# Qwiic_Solid_State_Relay.net
KiCad netlist of a schematic drawn in EAGLE
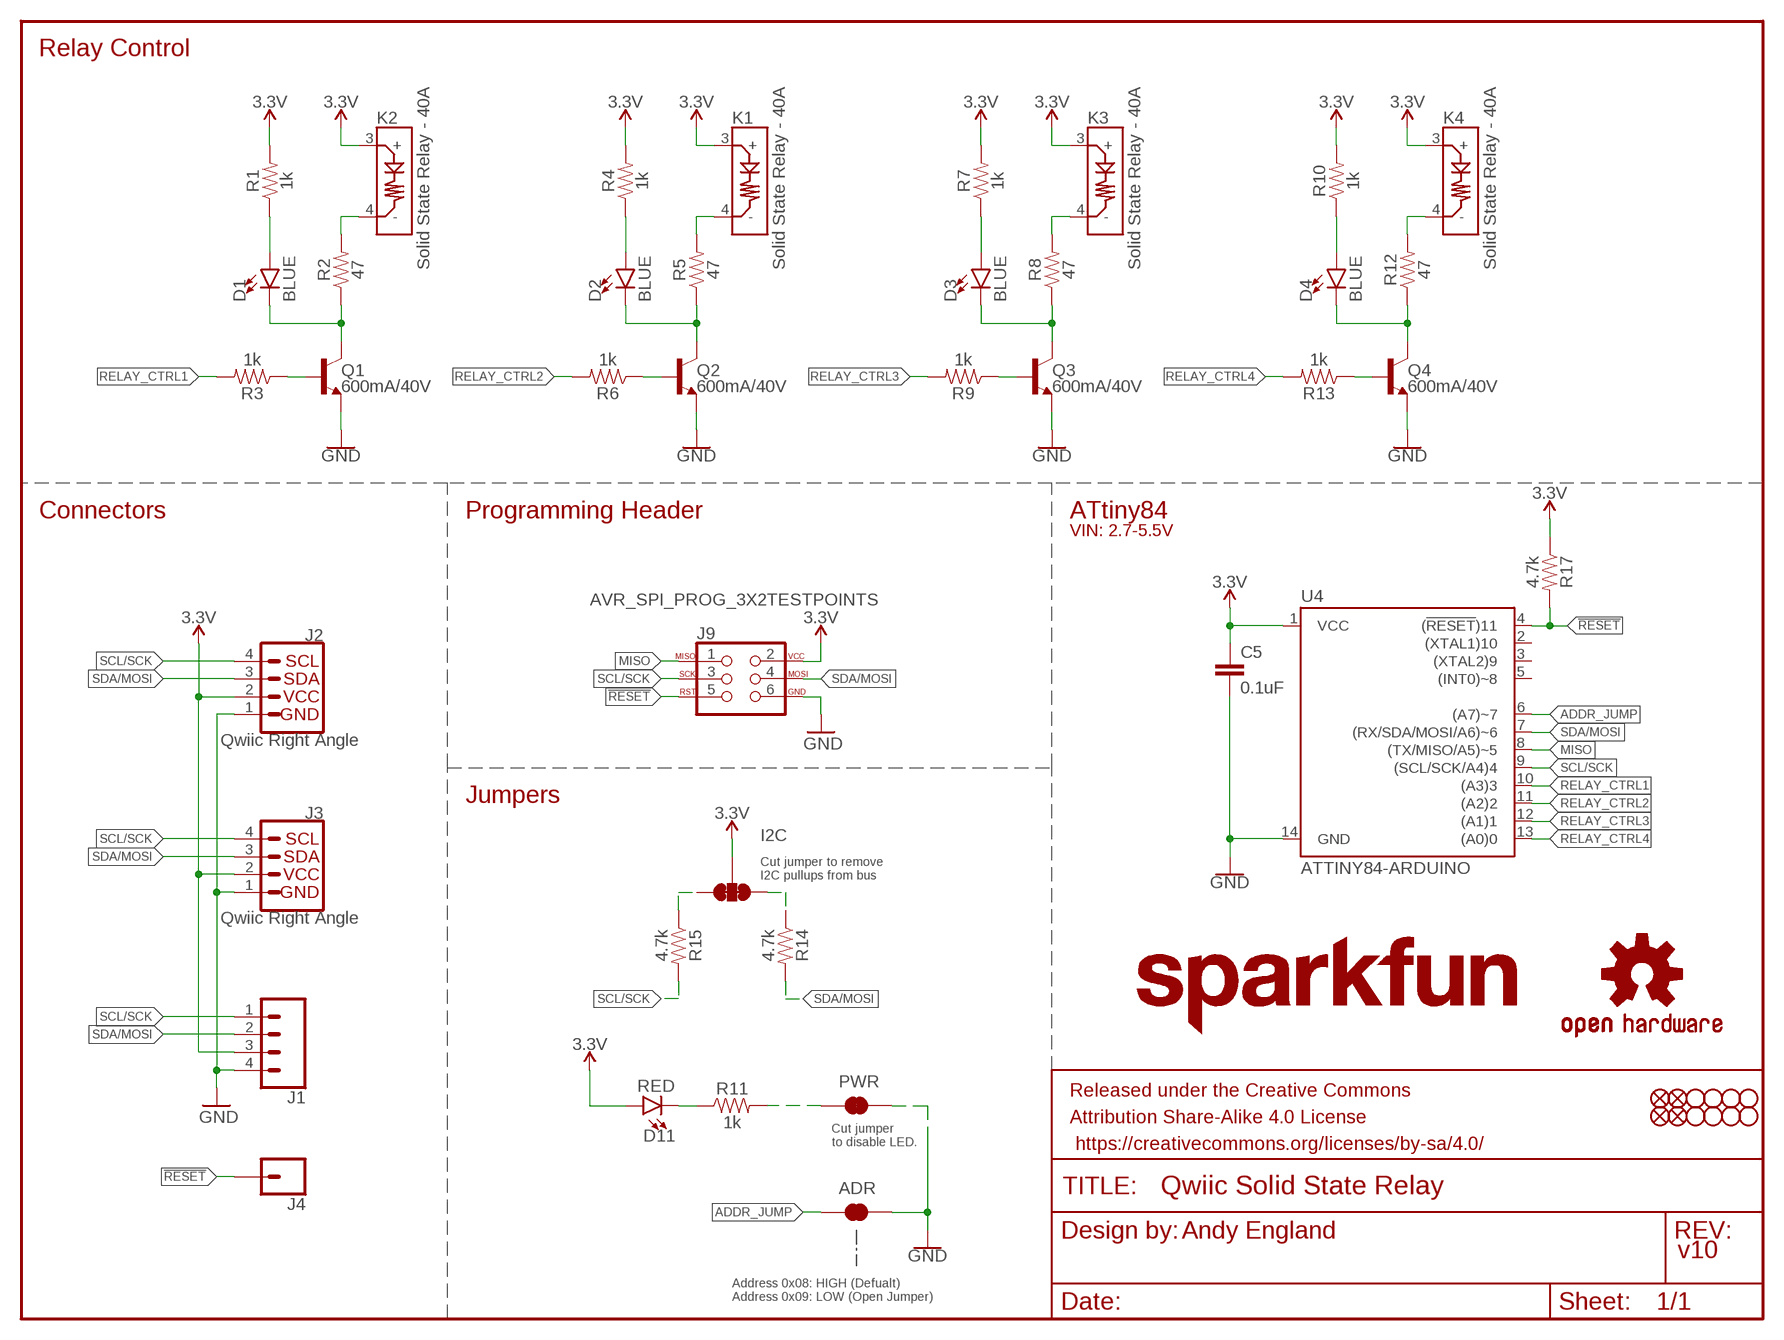
[diagram p0: schematic, sheet 1]

(export (version "E")
  (design (tool "Eeschema 10.0.6"))
  (components
    (comp (ref "ADR")
      (value "JUMPER-SMT_2_NC_TRACE_SILK")
      (footprint "eagle-import:SMT-JUMPER_2_NC_TRACE_SILK")
      (libsource (lib "eagle-import") (part "JUMPER-SMT_2_NC_TRACE_SILK"))
    )
    (comp (ref "C5")
      (value "0.1uF")
      (footprint "eagle-import:0603")
      (libsource (lib "eagle-import") (part "0.1UF-0603-25V-(+80/-20%)"))
    )
    (comp (ref "D1")
      (value "BLUE")
      (footprint "eagle-import:LED-0603")
      (libsource (lib "eagle-import") (part "LED-BLUE0603"))
    )
    (comp (ref "D2")
      (value "BLUE")
      (footprint "eagle-import:LED-0603")
      (libsource (lib "eagle-import") (part "LED-BLUE0603"))
    )
    (comp (ref "D3")
      (value "BLUE")
      (footprint "eagle-import:LED-0603")
      (libsource (lib "eagle-import") (part "LED-BLUE0603"))
    )
    (comp (ref "D4")
      (value "BLUE")
      (footprint "eagle-import:LED-0603")
      (libsource (lib "eagle-import") (part "LED-BLUE0603"))
    )
    (comp (ref "D11")
      (value "RED")
      (footprint "eagle-import:LED-0603")
      (libsource (lib "eagle-import") (part "LED-RED0603"))
    )
    (comp (ref "FD1")
      (value "FIDUCIAL1X2")
      (footprint "eagle-import:FIDUCIAL-1X2")
      (libsource (lib "eagle-import") (part "FIDUCIAL1X2"))
    )
    (comp (ref "FD2")
      (value "FIDUCIAL1X2")
      (footprint "eagle-import:FIDUCIAL-1X2")
      (libsource (lib "eagle-import") (part "FIDUCIAL1X2"))
    )
    (comp (ref "FD3")
      (value "FIDUCIAL1X2")
      (footprint "eagle-import:FIDUCIAL-1X2")
      (libsource (lib "eagle-import") (part "FIDUCIAL1X2"))
    )
    (comp (ref "FD4")
      (value "FIDUCIAL1X2")
      (footprint "eagle-import:FIDUCIAL-1X2")
      (libsource (lib "eagle-import") (part "FIDUCIAL1X2"))
    )
    (comp (ref "FRAME1")
      (value "FRAME-LETTER")
      (footprint "eagle-import:CREATIVE_COMMONS")
      (libsource (lib "eagle-import") (part "FRAME-LETTER"))
    )
    (comp (ref "I2C")
      (value "JUMPER-SMT_3_2-NC_TRACE_SILK")
      (footprint "eagle-import:SMT-JUMPER_3_2-NC_TRACE_SILK")
      (libsource (lib "eagle-import") (part "JUMPER-SMT_3_2-NC_TRACE_SILK"))
    )
    (comp (ref "J1")
      (value "CONN_041X04_NO_SILK")
      (footprint "eagle-import:1X04_NO_SILK")
      (libsource (lib "eagle-import") (part "CONN_041X04_NO_SILK"))
    )
    (comp (ref "J2")
      (value "Qwiic Right Angle")
      (footprint "eagle-import:JST04_1MM_RA")
      (libsource (lib "eagle-import") (part "I2C_STANDARDQWIIC"))
    )
    (comp (ref "J3")
      (value "Qwiic Right Angle")
      (footprint "eagle-import:JST04_1MM_RA")
      (libsource (lib "eagle-import") (part "I2C_STANDARDQWIIC"))
    )
    (comp (ref "J4")
      (value "CONN_01PTH_NO_SILK_YES_STOP")
      (footprint "eagle-import:1X01_NO_SILK")
      (libsource (lib "eagle-import") (part "CONN_01PTH_NO_SILK_YES_STOP"))
    )
    (comp (ref "J9")
      (value "AVR_SPI_PROG_3X2TESTPOINTS")
      (footprint "eagle-import:2X3_TEST_POINTS")
      (libsource (lib "eagle-import") (part "AVR_SPI_PROG_3X2TESTPOINTS"))
    )
    (comp (ref "JP1")
      (value "STAND-OFF")
      (footprint "eagle-import:STAND-OFF")
      (libsource (lib "eagle-import") (part "STAND-OFF"))
    )
    (comp (ref "JP2")
      (value "STAND-OFF")
      (footprint "eagle-import:STAND-OFF")
      (libsource (lib "eagle-import") (part "STAND-OFF"))
    )
    (comp (ref "JP3")
      (value "STAND-OFF")
      (footprint "eagle-import:STAND-OFF")
      (libsource (lib "eagle-import") (part "STAND-OFF"))
    )
    (comp (ref "JP4")
      (value "STAND-OFF")
      (footprint "eagle-import:STAND-OFF")
      (libsource (lib "eagle-import") (part "STAND-OFF"))
    )
    (comp (ref "JP5")
      (value "STAND-OFF")
      (footprint "eagle-import:STAND-OFF")
      (libsource (lib "eagle-import") (part "STAND-OFF"))
    )
    (comp (ref "JP6")
      (value "STAND-OFF")
      (footprint "eagle-import:STAND-OFF")
      (libsource (lib "eagle-import") (part "STAND-OFF"))
    )
    (comp (ref "JP7")
      (value "STAND-OFF")
      (footprint "eagle-import:STAND-OFF")
      (libsource (lib "eagle-import") (part "STAND-OFF"))
    )
    (comp (ref "JP8")
      (value "STAND-OFF")
      (footprint "eagle-import:STAND-OFF")
      (libsource (lib "eagle-import") (part "STAND-OFF"))
    )
    (comp (ref "K1")
      (value "Solid State Relay - 40A")
      (footprint "eagle-import:SSR-40DA-H")
      (libsource (lib "eagle-import") (part "SOLID_STATE_RELAY_SSR-40DA-H"))
    )
    (comp (ref "K2")
      (value "Solid State Relay - 40A")
      (footprint "eagle-import:SSR-40DA-H")
      (libsource (lib "eagle-import") (part "SOLID_STATE_RELAY_SSR-40DA-H"))
    )
    (comp (ref "K3")
      (value "Solid State Relay - 40A")
      (footprint "eagle-import:SSR-40DA-H")
      (libsource (lib "eagle-import") (part "SOLID_STATE_RELAY_SSR-40DA-H"))
    )
    (comp (ref "K4")
      (value "Solid State Relay - 40A")
      (footprint "eagle-import:SSR-40DA-H")
      (libsource (lib "eagle-import") (part "SOLID_STATE_RELAY_SSR-40DA-H"))
    )
    (comp (ref "LOGO1")
      (value "SFE_LOGO_NAME1_INCH")
      (footprint "eagle-import:SFE_LOGO_NAME_1")
      (libsource (lib "eagle-import") (part "SFE_LOGO_NAME1_INCH"))
    )
    (comp (ref "LOGO2")
      (value "OSHW-LOGOS")
      (footprint "eagle-import:OSHW-LOGO-S")
      (libsource (lib "eagle-import") (part "OSHW-LOGOS"))
    )
    (comp (ref "PWR")
      (value "JUMPER-SMT_2_NC_TRACE_SILK")
      (footprint "eagle-import:SMT-JUMPER_2_NC_TRACE_SILK")
      (libsource (lib "eagle-import") (part "JUMPER-SMT_2_NC_TRACE_SILK"))
    )
    (comp (ref "Q1")
      (value "600mA/40V")
      (footprint "eagle-import:SOT23-3")
      (libsource (lib "eagle-import") (part "TRANS_NPN-MMBT2222AL"))
    )
    (comp (ref "Q2")
      (value "600mA/40V")
      (footprint "eagle-import:SOT23-3")
      (libsource (lib "eagle-import") (part "TRANS_NPN-MMBT2222AL"))
    )
    (comp (ref "Q3")
      (value "600mA/40V")
      (footprint "eagle-import:SOT23-3")
      (libsource (lib "eagle-import") (part "TRANS_NPN-MMBT2222AL"))
    )
    (comp (ref "Q4")
      (value "600mA/40V")
      (footprint "eagle-import:SOT23-3")
      (libsource (lib "eagle-import") (part "TRANS_NPN-MMBT2222AL"))
    )
    (comp (ref "R1")
      (value "1k")
      (footprint "eagle-import:0603")
      (libsource (lib "eagle-import") (part "1KOHM-0603-1/10W-1%"))
    )
    (comp (ref "R2")
      (value "47")
      (footprint "eagle-import:0603")
      (libsource (lib "eagle-import") (part "47OHM-0603-1/10W-1%"))
    )
    (comp (ref "R3")
      (value "1k")
      (footprint "eagle-import:0603")
      (libsource (lib "eagle-import") (part "1KOHM-0603-1/10W-1%"))
    )
    (comp (ref "R4")
      (value "1k")
      (footprint "eagle-import:0603")
      (libsource (lib "eagle-import") (part "1KOHM-0603-1/10W-1%"))
    )
    (comp (ref "R5")
      (value "47")
      (footprint "eagle-import:0603")
      (libsource (lib "eagle-import") (part "47OHM-0603-1/10W-1%"))
    )
    (comp (ref "R6")
      (value "1k")
      (footprint "eagle-import:0603")
      (libsource (lib "eagle-import") (part "1KOHM-0603-1/10W-1%"))
    )
    (comp (ref "R7")
      (value "1k")
      (footprint "eagle-import:0603")
      (libsource (lib "eagle-import") (part "1KOHM-0603-1/10W-1%"))
    )
    (comp (ref "R8")
      (value "47")
      (footprint "eagle-import:0603")
      (libsource (lib "eagle-import") (part "47OHM-0603-1/10W-1%"))
    )
    (comp (ref "R9")
      (value "1k")
      (footprint "eagle-import:0603")
      (libsource (lib "eagle-import") (part "1KOHM-0603-1/10W-1%"))
    )
    (comp (ref "R10")
      (value "1k")
      (footprint "eagle-import:0603")
      (libsource (lib "eagle-import") (part "1KOHM-0603-1/10W-1%"))
    )
    (comp (ref "R11")
      (value "1k")
      (footprint "eagle-import:0603")
      (libsource (lib "eagle-import") (part "1KOHM-0603-1/10W-1%"))
    )
    (comp (ref "R12")
      (value "47")
      (footprint "eagle-import:0603")
      (libsource (lib "eagle-import") (part "47OHM-0603-1/10W-1%"))
    )
    (comp (ref "R13")
      (value "1k")
      (footprint "eagle-import:0603")
      (libsource (lib "eagle-import") (part "1KOHM-0603-1/10W-1%"))
    )
    (comp (ref "R14")
      (value "4.7k")
      (footprint "eagle-import:0603")
      (libsource (lib "eagle-import") (part "4.7KOHM-0603-1/10W-1%"))
    )
    (comp (ref "R15")
      (value "4.7k")
      (footprint "eagle-import:0603")
      (libsource (lib "eagle-import") (part "4.7KOHM-0603-1/10W-1%"))
    )
    (comp (ref "R17")
      (value "4.7k")
      (footprint "eagle-import:0603")
      (libsource (lib "eagle-import") (part "4.7KOHM-0603-1/10W-1%"))
    )
    (comp (ref "U4")
      (value "ATTINY84-ARDUINO")
      (footprint "eagle-import:SO14")
      (libsource (lib "eagle-import") (part "ATTINY84-ARDUINO"))
    )
  )
  (nets
    (net (code "1") (name "/~{RESET}") (class "Default")
      (node (ref "J4") (pin "1") (pinfunction "1_1") (pintype "passive"))
      (node (ref "J9") (pin "5") (pinfunction "5_5") (pintype "passive"))
      (node (ref "R17") (pin "2") (pinfunction "2_2") (pintype "passive"))
      (node (ref "U4") (pin "4") (pinfunction "(~{RESET})11_4") (pintype "bidirectional"))
    )
    (net (code "2") (name "3.3V") (class "Default")
      (node (ref "C5") (pin "1") (pinfunction "1_1") (pintype "passive"))
      (node (ref "D11") (pin "A") (pinfunction "A_A") (pintype "passive"))
      (node (ref "I2C") (pin "2") (pinfunction "2_2") (pintype "passive"))
      (node (ref "J1") (pin "3") (pinfunction "3_3") (pintype "passive"))
      (node (ref "J2") (pin "2") (pinfunction "2_2") (pintype "power_in"))
      (node (ref "J3") (pin "2") (pinfunction "2_2") (pintype "power_in"))
      (node (ref "J9") (pin "2") (pinfunction "2_2") (pintype "passive"))
      (node (ref "K1") (pin "3") (pinfunction "+_3") (pintype "bidirectional"))
      (node (ref "K2") (pin "3") (pinfunction "+_3") (pintype "bidirectional"))
      (node (ref "K3") (pin "3") (pinfunction "+_3") (pintype "bidirectional"))
      (node (ref "K4") (pin "3") (pinfunction "+_3") (pintype "bidirectional"))
      (node (ref "R1") (pin "2") (pinfunction "2_2") (pintype "passive"))
      (node (ref "R10") (pin "2") (pinfunction "2_2") (pintype "passive"))
      (node (ref "R17") (pin "1") (pinfunction "1_1") (pintype "passive"))
      (node (ref "R4") (pin "2") (pinfunction "2_2") (pintype "passive"))
      (node (ref "R7") (pin "2") (pinfunction "2_2") (pintype "passive"))
      (node (ref "U4") (pin "1") (pinfunction "VCC_1") (pintype "bidirectional"))
    )
    (net (code "3") (name "ADDR_JUMP") (class "Default")
      (node (ref "ADR") (pin "1") (pinfunction "1_1") (pintype "passive"))
      (node (ref "U4") (pin "6") (pinfunction "(A7)~{7}_6") (pintype "bidirectional"))
    )
    (net (code "4") (name "GND") (class "Default")
      (node (ref "ADR") (pin "2") (pinfunction "2_2") (pintype "passive"))
      (node (ref "C5") (pin "2") (pinfunction "2_2") (pintype "passive"))
      (node (ref "J1") (pin "4") (pinfunction "4_4") (pintype "passive"))
      (node (ref "J2") (pin "1") (pinfunction "1_1") (pintype "power_in"))
      (node (ref "J3") (pin "1") (pinfunction "1_1") (pintype "power_in"))
      (node (ref "J9") (pin "6") (pinfunction "6_6") (pintype "passive"))
      (node (ref "PWR") (pin "1") (pinfunction "1_1") (pintype "passive"))
      (node (ref "Q1") (pin "2") (pinfunction "E_2") (pintype "passive"))
      (node (ref "Q2") (pin "2") (pinfunction "E_2") (pintype "passive"))
      (node (ref "Q3") (pin "2") (pinfunction "E_2") (pintype "passive"))
      (node (ref "Q4") (pin "2") (pinfunction "E_2") (pintype "passive"))
      (node (ref "U4") (pin "14") (pinfunction "GND_14") (pintype "bidirectional"))
    )
    (net (code "5") (name "MISO") (class "Default")
      (node (ref "J9") (pin "1") (pinfunction "1_1") (pintype "passive"))
      (node (ref "U4") (pin "8") (pinfunction "(TX/MISO/A5)~{5}_8") (pintype "bidirectional"))
    )
    (net (code "6") (name "Net-(D1-PadA)") (class "Default")
      (node (ref "D1") (pin "A") (pinfunction "A_A") (pintype "passive"))
      (node (ref "R1") (pin "1") (pinfunction "1_1") (pintype "passive"))
    )
    (net (code "7") (name "Net-(D2-PadA)") (class "Default")
      (node (ref "D2") (pin "A") (pinfunction "A_A") (pintype "passive"))
      (node (ref "R4") (pin "1") (pinfunction "1_1") (pintype "passive"))
    )
    (net (code "8") (name "Net-(D3-PadA)") (class "Default")
      (node (ref "D3") (pin "A") (pinfunction "A_A") (pintype "passive"))
      (node (ref "R7") (pin "1") (pinfunction "1_1") (pintype "passive"))
    )
    (net (code "9") (name "Net-(D4-PadA)") (class "Default")
      (node (ref "D4") (pin "A") (pinfunction "A_A") (pintype "passive"))
      (node (ref "R10") (pin "1") (pinfunction "1_1") (pintype "passive"))
    )
    (net (code "10") (name "Net-(D11-PadC)") (class "Default")
      (node (ref "D11") (pin "C") (pinfunction "C_C") (pintype "passive"))
      (node (ref "R11") (pin "1") (pinfunction "1_1") (pintype "passive"))
    )
    (net (code "11") (name "Net-(I2C-Pad1)") (class "Default")
      (node (ref "I2C") (pin "1") (pinfunction "1_1") (pintype "passive"))
      (node (ref "R14") (pin "1") (pinfunction "1_1") (pintype "passive"))
    )
    (net (code "12") (name "Net-(I2C-Pad3)") (class "Default")
      (node (ref "I2C") (pin "3") (pinfunction "3_3") (pintype "passive"))
      (node (ref "R15") (pin "1") (pinfunction "1_1") (pintype "passive"))
    )
    (net (code "13") (name "Net-(K1--)") (class "Default")
      (node (ref "K1") (pin "4") (pinfunction "-_4") (pintype "bidirectional"))
      (node (ref "R5") (pin "2") (pinfunction "2_2") (pintype "passive"))
    )
    (net (code "14") (name "Net-(K2--)") (class "Default")
      (node (ref "K2") (pin "4") (pinfunction "-_4") (pintype "bidirectional"))
      (node (ref "R2") (pin "2") (pinfunction "2_2") (pintype "passive"))
    )
    (net (code "15") (name "Net-(K3--)") (class "Default")
      (node (ref "K3") (pin "4") (pinfunction "-_4") (pintype "bidirectional"))
      (node (ref "R8") (pin "2") (pinfunction "2_2") (pintype "passive"))
    )
    (net (code "16") (name "Net-(K4--)") (class "Default")
      (node (ref "K4") (pin "4") (pinfunction "-_4") (pintype "bidirectional"))
      (node (ref "R12") (pin "2") (pinfunction "2_2") (pintype "passive"))
    )
    (net (code "17") (name "Net-(PWR-Pad2)") (class "Default")
      (node (ref "PWR") (pin "2") (pinfunction "2_2") (pintype "passive"))
      (node (ref "R11") (pin "2") (pinfunction "2_2") (pintype "passive"))
    )
    (net (code "18") (name "Net-(Q1-B)") (class "Default")
      (node (ref "Q1") (pin "1") (pinfunction "B_1") (pintype "passive"))
      (node (ref "R3") (pin "1") (pinfunction "1_1") (pintype "passive"))
    )
    (net (code "19") (name "Net-(Q1-C)") (class "Default")
      (node (ref "D1") (pin "C") (pinfunction "C_C") (pintype "passive"))
      (node (ref "Q1") (pin "3") (pinfunction "C_3") (pintype "passive"))
      (node (ref "R2") (pin "1") (pinfunction "1_1") (pintype "passive"))
    )
    (net (code "20") (name "Net-(Q2-B)") (class "Default")
      (node (ref "Q2") (pin "1") (pinfunction "B_1") (pintype "passive"))
      (node (ref "R6") (pin "1") (pinfunction "1_1") (pintype "passive"))
    )
    (net (code "21") (name "Net-(Q2-C)") (class "Default")
      (node (ref "D2") (pin "C") (pinfunction "C_C") (pintype "passive"))
      (node (ref "Q2") (pin "3") (pinfunction "C_3") (pintype "passive"))
      (node (ref "R5") (pin "1") (pinfunction "1_1") (pintype "passive"))
    )
    (net (code "22") (name "Net-(Q3-B)") (class "Default")
      (node (ref "Q3") (pin "1") (pinfunction "B_1") (pintype "passive"))
      (node (ref "R9") (pin "1") (pinfunction "1_1") (pintype "passive"))
    )
    (net (code "23") (name "Net-(Q3-C)") (class "Default")
      (node (ref "D3") (pin "C") (pinfunction "C_C") (pintype "passive"))
      (node (ref "Q3") (pin "3") (pinfunction "C_3") (pintype "passive"))
      (node (ref "R8") (pin "1") (pinfunction "1_1") (pintype "passive"))
    )
    (net (code "24") (name "Net-(Q4-B)") (class "Default")
      (node (ref "Q4") (pin "1") (pinfunction "B_1") (pintype "passive"))
      (node (ref "R13") (pin "1") (pinfunction "1_1") (pintype "passive"))
    )
    (net (code "25") (name "Net-(Q4-C)") (class "Default")
      (node (ref "D4") (pin "C") (pinfunction "C_C") (pintype "passive"))
      (node (ref "Q4") (pin "3") (pinfunction "C_3") (pintype "passive"))
      (node (ref "R12") (pin "1") (pinfunction "1_1") (pintype "passive"))
    )
    (net (code "26") (name "RELAY_CTRL1") (class "Default")
      (node (ref "R3") (pin "2") (pinfunction "2_2") (pintype "passive"))
      (node (ref "U4") (pin "10") (pinfunction "(A3)3_10") (pintype "bidirectional"))
    )
    (net (code "27") (name "RELAY_CTRL2") (class "Default")
      (node (ref "R6") (pin "2") (pinfunction "2_2") (pintype "passive"))
      (node (ref "U4") (pin "11") (pinfunction "(A2)2_11") (pintype "bidirectional"))
    )
    (net (code "28") (name "RELAY_CTRL3") (class "Default")
      (node (ref "R9") (pin "2") (pinfunction "2_2") (pintype "passive"))
      (node (ref "U4") (pin "12") (pinfunction "(A1)1_12") (pintype "bidirectional"))
    )
    (net (code "29") (name "RELAY_CTRL4") (class "Default")
      (node (ref "R13") (pin "2") (pinfunction "2_2") (pintype "passive"))
      (node (ref "U4") (pin "13") (pinfunction "(A0)0_13") (pintype "bidirectional"))
    )
    (net (code "30") (name "SCL{slash}SCK") (class "Default")
      (node (ref "J1") (pin "1") (pinfunction "1_1") (pintype "passive"))
      (node (ref "J2") (pin "4") (pinfunction "4_4") (pintype "passive"))
      (node (ref "J3") (pin "4") (pinfunction "4_4") (pintype "passive"))
      (node (ref "J9") (pin "3") (pinfunction "3_3") (pintype "passive"))
      (node (ref "R15") (pin "2") (pinfunction "2_2") (pintype "passive"))
      (node (ref "U4") (pin "9") (pinfunction "(SCL/SCK/A4)4_9") (pintype "bidirectional"))
    )
    (net (code "31") (name "SDA{slash}MOSI") (class "Default")
      (node (ref "J1") (pin "2") (pinfunction "2_2") (pintype "passive"))
      (node (ref "J2") (pin "3") (pinfunction "3_3") (pintype "passive"))
      (node (ref "J3") (pin "3") (pinfunction "3_3") (pintype "passive"))
      (node (ref "J9") (pin "4") (pinfunction "4_4") (pintype "passive"))
      (node (ref "R14") (pin "2") (pinfunction "2_2") (pintype "passive"))
      (node (ref "U4") (pin "7") (pinfunction "(RX/SDA/MOSI/A6)~{6}_7") (pintype "bidirectional"))
    )
    (net (code "32") (name "unconnected-(U4-(INT0)~{8}-Pad5)") (class "Default")
      (node (ref "U4") (pin "5") (pinfunction "(INT0)~{8}_5") (pintype "bidirectional"))
    )
    (net (code "33") (name "unconnected-(U4-(XTAL1)10-Pad2)") (class "Default")
      (node (ref "U4") (pin "2") (pinfunction "(XTAL1)10_2") (pintype "bidirectional"))
    )
    (net (code "34") (name "unconnected-(U4-(XTAL2)9-Pad3)") (class "Default")
      (node (ref "U4") (pin "3") (pinfunction "(XTAL2)9_3") (pintype "bidirectional"))
    )
  )
)
